# BATT_CPU.net
KiCad netlist of a schematic drawn in EAGLE
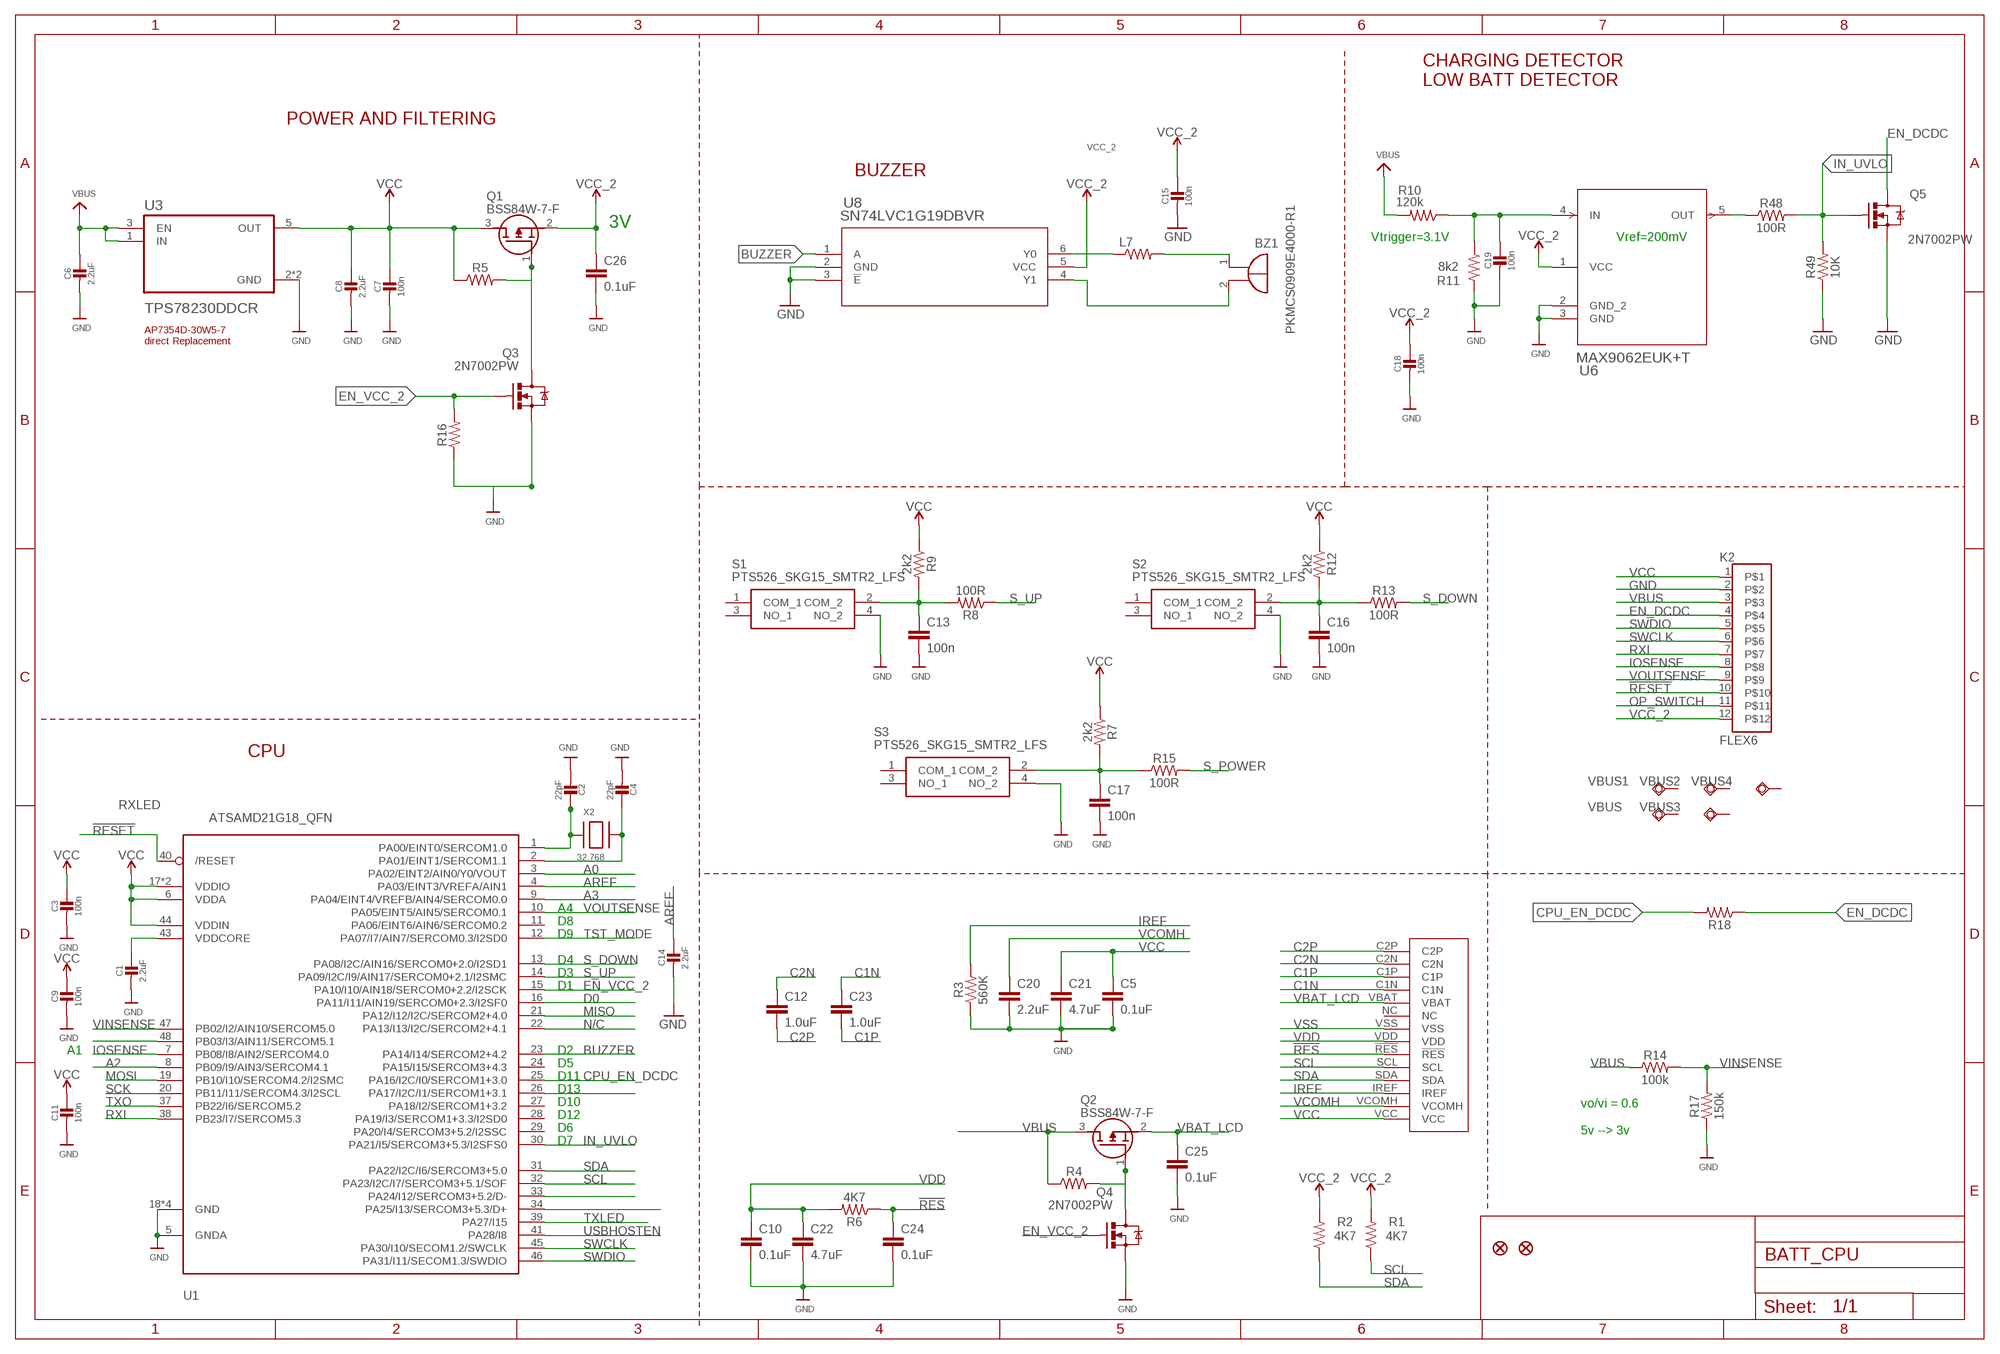
[diagram p0: schematic, sheet 1]

(export (version "E")
  (design (tool "Eeschema 10.0.6"))
  (components
    (comp (ref "BZ1")
      (value "PKMCS0909E4000-R1")
      (footprint "eagle-import:PKMCS0909")
      (libsource (lib "eagle-import") (part "PKMCS0909E4000-R1"))
    )
    (comp (ref "C1")
      (value "2.2uF")
      (footprint "eagle-import:0603-NO")
      (libsource (lib "eagle-import") (part "CAP_CERAMIC0603_NO"))
    )
    (comp (ref "C2")
      (value "22pF")
      (footprint "eagle-import:0603-NO")
      (libsource (lib "eagle-import") (part "CAP_CERAMIC0603_NO"))
    )
    (comp (ref "C3")
      (value "100n")
      (footprint "eagle-import:0603-NO")
      (libsource (lib "eagle-import") (part "CAP_CERAMIC0603_NO"))
    )
    (comp (ref "C4")
      (value "22pF")
      (footprint "eagle-import:0603-NO")
      (libsource (lib "eagle-import") (part "CAP_CERAMIC0603_NO"))
    )
    (comp (ref "C5")
      (value "0.1uF")
      (footprint "eagle-import:0402")
      (libsource (lib "eagle-import") (part "0.1UF-0402-16V-10%"))
    )
    (comp (ref "C6")
      (value "2.2uF")
      (footprint "eagle-import:0805-NO")
      (libsource (lib "eagle-import") (part "CAP_CERAMIC0805-NOOUTLINE"))
    )
    (comp (ref "C7")
      (value "100n")
      (footprint "eagle-import:0603-NO")
      (libsource (lib "eagle-import") (part "CAP_CERAMIC0603_NO"))
    )
    (comp (ref "C8")
      (value "2.2uF")
      (footprint "eagle-import:0805-NO")
      (libsource (lib "eagle-import") (part "CAP_CERAMIC0805-NOOUTLINE"))
    )
    (comp (ref "C9")
      (value "100n")
      (footprint "eagle-import:0603-NO")
      (libsource (lib "eagle-import") (part "CAP_CERAMIC0603_NO"))
    )
    (comp (ref "C10")
      (value "0.1uF")
      (footprint "eagle-import:0402")
      (libsource (lib "eagle-import") (part "0.1UF-0402-16V-10%"))
    )
    (comp (ref "C11")
      (value "100n")
      (footprint "eagle-import:0603-NO")
      (libsource (lib "eagle-import") (part "CAP_CERAMIC0603_NO"))
    )
    (comp (ref "C12")
      (value "1.0uF")
      (footprint "eagle-import:0402")
      (libsource (lib "eagle-import") (part "1.0UF-0402-16V-10%"))
    )
    (comp (ref "C13")
      (value "100n")
      (footprint "eagle-import:C0805")
      (libsource (lib "eagle-import") (part "C-EUC0805"))
    )
    (comp (ref "C14")
      (value "2.2uF")
      (footprint "eagle-import:0603-NO")
      (libsource (lib "eagle-import") (part "CAP_CERAMIC0603_NO"))
    )
    (comp (ref "C15")
      (value "100n")
      (footprint "eagle-import:0603-NO")
      (libsource (lib "eagle-import") (part "CAP_CERAMIC0603_NO"))
    )
    (comp (ref "C16")
      (value "100n")
      (footprint "eagle-import:C0805")
      (libsource (lib "eagle-import") (part "C-EUC0805"))
    )
    (comp (ref "C17")
      (value "100n")
      (footprint "eagle-import:C0805")
      (libsource (lib "eagle-import") (part "C-EUC0805"))
    )
    (comp (ref "C18")
      (value "100n")
      (footprint "eagle-import:0603-NO")
      (libsource (lib "eagle-import") (part "CAP_CERAMIC0603_NO"))
    )
    (comp (ref "C19")
      (value "100n")
      (footprint "eagle-import:0603-NO")
      (libsource (lib "eagle-import") (part "CAP_CERAMIC0603_NO"))
    )
    (comp (ref "C20")
      (value "2.2uF")
      (footprint "eagle-import:0603")
      (libsource (lib "eagle-import") (part "2.2UF-0603-10V-20%"))
    )
    (comp (ref "C21")
      (value "4.7uF")
      (footprint "eagle-import:0603")
      (libsource (lib "eagle-import") (part "4.7UF0603"))
    )
    (comp (ref "C22")
      (value "4.7uF")
      (footprint "eagle-import:0603")
      (libsource (lib "eagle-import") (part "4.7UF0603"))
    )
    (comp (ref "C23")
      (value "1.0uF")
      (footprint "eagle-import:0402")
      (libsource (lib "eagle-import") (part "1.0UF-0402-16V-10%"))
    )
    (comp (ref "C24")
      (value "0.1uF")
      (footprint "eagle-import:0402")
      (libsource (lib "eagle-import") (part "0.1UF-0402-16V-10%"))
    )
    (comp (ref "C25")
      (value "0.1uF")
      (footprint "eagle-import:0402")
      (libsource (lib "eagle-import") (part "0.1UF-0402-16V-10%"))
    )
    (comp (ref "C26")
      (value "0.1uF")
      (footprint "eagle-import:0402")
      (libsource (lib "eagle-import") (part "0.1UF-0402-16V-10%"))
    )
    (comp (ref "K2")
      (value "FLEX6")
      (footprint "eagle-import:FLEX6")
      (libsource (lib "eagle-import") (part "FLEX6"))
    )
    (comp (ref "L7")
      (value "MMZ2012Y202BT000")
      (footprint "eagle-import:0805")
      (libsource (lib "eagle-import") (part "RESISTOR0805-RES"))
    )
    (comp (ref "Q1")
      (value "BSS84W-7-F")
      (footprint "eagle-import:SOT65P222X110-3N")
      (libsource (lib "eagle-import") (part "BSS84W-7-F"))
    )
    (comp (ref "Q2")
      (value "BSS84W-7-F")
      (footprint "eagle-import:SOT65P222X110-3N")
      (libsource (lib "eagle-import") (part "BSS84W-7-F"))
    )
    (comp (ref "Q3")
      (value "2N7002PW")
      (footprint "eagle-import:SOT323")
      (libsource (lib "eagle-import") (part "MOSFET-NCHANNEL2N7002PW"))
    )
    (comp (ref "Q4")
      (value "2N7002PW")
      (footprint "eagle-import:SOT323")
      (libsource (lib "eagle-import") (part "MOSFET-NCHANNEL2N7002PW"))
    )
    (comp (ref "Q5")
      (value "2N7002PW")
      (footprint "eagle-import:SOT323")
      (libsource (lib "eagle-import") (part "MOSFET-NCHANNEL2N7002PW"))
    )
    (comp (ref "R1")
      (value "4K7")
      (footprint "eagle-import:0402")
      (libsource (lib "eagle-import") (part "RESISTOR0402"))
    )
    (comp (ref "R2")
      (value "4K7")
      (footprint "eagle-import:0402")
      (libsource (lib "eagle-import") (part "RESISTOR0402"))
    )
    (comp (ref "R3")
      (value "560K")
      (footprint "eagle-import:0402")
      (libsource (lib "eagle-import") (part "RESISTOR0402"))
    )
    (comp (ref "R4")
      (value "RESISTOR0402")
      (footprint "eagle-import:0402")
      (libsource (lib "eagle-import") (part "RESISTOR0402"))
    )
    (comp (ref "R5")
      (value "RESISTOR0402")
      (footprint "eagle-import:0402")
      (libsource (lib "eagle-import") (part "RESISTOR0402"))
    )
    (comp (ref "R6")
      (value "4K7")
      (footprint "eagle-import:0402")
      (libsource (lib "eagle-import") (part "RESISTOR0402"))
    )
    (comp (ref "R7")
      (value "2k2")
      (footprint "eagle-import:0402")
      (libsource (lib "eagle-import") (part "RESISTOR0402"))
    )
    (comp (ref "R8")
      (value "100R")
      (footprint "eagle-import:0402")
      (libsource (lib "eagle-import") (part "RESISTOR0402"))
    )
    (comp (ref "R9")
      (value "2k2")
      (footprint "eagle-import:0402")
      (libsource (lib "eagle-import") (part "RESISTOR0402"))
    )
    (comp (ref "R10")
      (value "120k")
      (footprint "eagle-import:0402")
      (libsource (lib "eagle-import") (part "RESISTOR0402"))
    )
    (comp (ref "R11")
      (value "8k2")
      (footprint "eagle-import:0402")
      (libsource (lib "eagle-import") (part "RESISTOR0402"))
    )
    (comp (ref "R12")
      (value "2k2")
      (footprint "eagle-import:0402")
      (libsource (lib "eagle-import") (part "RESISTOR0402"))
    )
    (comp (ref "R13")
      (value "100R")
      (footprint "eagle-import:0402")
      (libsource (lib "eagle-import") (part "RESISTOR0402"))
    )
    (comp (ref "R14")
      (value "100k")
      (footprint "eagle-import:0402")
      (libsource (lib "eagle-import") (part "RESISTOR0402"))
    )
    (comp (ref "R15")
      (value "100R")
      (footprint "eagle-import:0402")
      (libsource (lib "eagle-import") (part "RESISTOR0402"))
    )
    (comp (ref "R16")
      (value "RESISTOR0402")
      (footprint "eagle-import:0402")
      (libsource (lib "eagle-import") (part "RESISTOR0402"))
    )
    (comp (ref "R17")
      (value "150k")
      (footprint "eagle-import:0402")
      (libsource (lib "eagle-import") (part "RESISTOR0402"))
    )
    (comp (ref "R18")
      (value "RESISTOR0402")
      (footprint "eagle-import:0402")
      (libsource (lib "eagle-import") (part "RESISTOR0402"))
    )
    (comp (ref "R48")
      (value "100R")
      (footprint "eagle-import:0402")
      (libsource (lib "eagle-import") (part "RESISTOR0402"))
    )
    (comp (ref "R49")
      (value "10K")
      (footprint "eagle-import:0402")
      (libsource (lib "eagle-import") (part "RESISTOR0402"))
    )
    (comp (ref "S1")
      (value "PTS526_SKG15_SMTR2_LFS")
      (footprint "eagle-import:PTS526SKG15SMTR2LFS")
      (fields
        (field (name "ARROW_PART_NUMBER") "PTS526 SKG15 SMTR2 LFS")
        (field (name "MOUSER_PART_NUMBER") "611-PTS526SKG15SMR2L")
      )
      (libsource (lib "eagle-import") (part "PTS526_SKG15_SMTR2_LFS"))
    )
    (comp (ref "S2")
      (value "PTS526_SKG15_SMTR2_LFS")
      (footprint "eagle-import:PTS526SKG15SMTR2LFS")
      (fields
        (field (name "ARROW_PART_NUMBER") "PTS526 SKG15 SMTR2 LFS")
        (field (name "MOUSER_PART_NUMBER") "611-PTS526SKG15SMR2L")
      )
      (libsource (lib "eagle-import") (part "PTS526_SKG15_SMTR2_LFS"))
    )
    (comp (ref "S3")
      (value "PTS526_SKG15_SMTR2_LFS")
      (footprint "eagle-import:PTS526SKG15SMTR2LFS")
      (fields
        (field (name "ARROW_PART_NUMBER") "PTS526 SKG15 SMTR2 LFS")
        (field (name "MOUSER_PART_NUMBER") "611-PTS526SKG15SMR2L")
      )
      (libsource (lib "eagle-import") (part "PTS526_SKG15_SMTR2_LFS"))
    )
    (comp (ref "U$30")
      (value "64X32_OLED_049")
      (footprint "eagle-import:LCD_14_PINS")
      (libsource (lib "eagle-import") (part "64X32_OLED_049"))
    )
    (comp (ref "U$34")
      (value "FIDUCIAL\"\"")
      (footprint "eagle-import:FIDUCIAL_1MM")
      (libsource (lib "eagle-import") (part "FIDUCIAL{dblquote}{dblquote}"))
    )
    (comp (ref "U$35")
      (value "FIDUCIAL\"\"")
      (footprint "eagle-import:FIDUCIAL_1MM")
      (libsource (lib "eagle-import") (part "FIDUCIAL{dblquote}{dblquote}"))
    )
    (comp (ref "U1")
      (value "ATSAMD21G18_QFN")
      (footprint "eagle-import:TQFN48_7MM")
      (libsource (lib "eagle-import") (part "ATSAMD21J_QFN"))
    )
    (comp (ref "U3")
      (value "TPS78230DDCR")
      (footprint "eagle-import:SOT95P280X110-5N")
      (fields (field (name "MF") "Texas Instruments"))
      (libsource (lib "eagle-import") (part "TPS78230DDCR"))
    )
    (comp (ref "U6")
      (value "MAX9062EUK+T")
      (footprint "eagle-import:21-0057F_MXM")
      (libsource (lib "eagle-import") (part "MAX9062EUK+T"))
    )
    (comp (ref "U8")
      (value "SN74LVC1G19DBVR")
      (footprint "eagle-import:DBV6")
      (fields
        (field (name "GENERIC_PART_NUMBER") "SN74LVC1G19")
        (field (name "MANUFACTURER") "Texas Instruments")
      )
      (libsource (lib "eagle-import") (part "SN74LVC1G19DBVR"))
    )
    (comp (ref "VBUS")
      (value "TESTPAD_TPSQB1,27")
      (footprint "eagle-import:TESTPAD_B1,27")
      (libsource (lib "eagle-import") (part "TESTPAD_TPSQB1,27"))
    )
    (comp (ref "VBUS1")
      (value "TESTPAD_TPSQB1,27")
      (footprint "eagle-import:TESTPAD_B1,27")
      (libsource (lib "eagle-import") (part "TESTPAD_TPSQB1,27"))
    )
    (comp (ref "VBUS2")
      (value "TESTPAD_TPSQB1,27")
      (footprint "eagle-import:TESTPAD_B1,27")
      (libsource (lib "eagle-import") (part "TESTPAD_TPSQB1,27"))
    )
    (comp (ref "VBUS3")
      (value "TESTPAD_TPSQB1,27")
      (footprint "eagle-import:TESTPAD_B1,27")
      (libsource (lib "eagle-import") (part "TESTPAD_TPSQB1,27"))
    )
    (comp (ref "VBUS4")
      (value "TESTPAD_TPSQB1,27")
      (footprint "eagle-import:TESTPAD_B1,27")
      (libsource (lib "eagle-import") (part "TESTPAD_TPSQB1,27"))
    )
    (comp (ref "X2")
      (value "32.768")
      (footprint "eagle-import:XTAL3215")
      (libsource (lib "eagle-import") (part "XTAL-3.2X1.5"))
    )
  )
  (nets
    (net (code "1") (name "/A0") (class "Default")
      (node (ref "U1") (pin "3") (pinfunction "PA02/EINT2/AIN0/Y0/VOUT_3") (pintype "bidirectional"))
    )
    (net (code "2") (name "/A2") (class "Default")
      (node (ref "U1") (pin "8") (pinfunction "PB09/I9/AIN3/SERCOM4.1_8") (pintype "bidirectional"))
    )
    (net (code "3") (name "/A3") (class "Default")
      (node (ref "U1") (pin "9") (pinfunction "PA04/EINT4/VREFB/AIN4/SERCOM0.0_9") (pintype "bidirectional"))
    )
    (net (code "4") (name "/AREF") (class "Default")
      (node (ref "C14") (pin "1") (pinfunction "1_1") (pintype "passive"))
      (node (ref "U1") (pin "4") (pinfunction "PA03/EINT3/VREFA/AIN1_4") (pintype "bidirectional"))
    )
    (net (code "5") (name "/C1N") (class "Default")
      (node (ref "C23") (pin "1") (pinfunction "1_1") (pintype "passive"))
      (node (ref "U$30") (pin "C1N") (pinfunction "C1N_C1N") (pintype "bidirectional"))
    )
    (net (code "6") (name "/C1P") (class "Default")
      (node (ref "C23") (pin "2") (pinfunction "2_2") (pintype "passive"))
      (node (ref "U$30") (pin "C1P") (pinfunction "C1P_C1P") (pintype "bidirectional"))
    )
    (net (code "7") (name "/C2N") (class "Default")
      (node (ref "C12") (pin "1") (pinfunction "1_1") (pintype "passive"))
      (node (ref "U$30") (pin "C2N") (pinfunction "C2N_C2N") (pintype "bidirectional"))
    )
    (net (code "8") (name "/C2P") (class "Default")
      (node (ref "C12") (pin "2") (pinfunction "2_2") (pintype "passive"))
      (node (ref "U$30") (pin "C2P") (pinfunction "C2P_C2P") (pintype "bidirectional"))
    )
    (net (code "9") (name "/D0") (class "Default")
      (node (ref "U1") (pin "16") (pinfunction "PA11/I11/AIN19/SERCOM0+2.3/I2SF0_16") (pintype "bidirectional"))
    )
    (net (code "10") (name "/IOSENSE") (class "Default")
      (node (ref "K2") (pin "8") (pinfunction "P$8_8") (pintype "bidirectional"))
      (node (ref "U1") (pin "7") (pinfunction "PB08/I8/AIN2/SERCOM4.0_7") (pintype "bidirectional"))
    )
    (net (code "11") (name "/IREF") (class "Default")
      (node (ref "R3") (pin "2") (pinfunction "2_2") (pintype "passive"))
      (node (ref "U$30") (pin "IREF") (pinfunction "IREF_IREF") (pintype "bidirectional"))
    )
    (net (code "12") (name "/MISO") (class "Default")
      (node (ref "U1") (pin "21") (pinfunction "PA12/I12/I2C/SERCOM2+4.0_21") (pintype "bidirectional"))
    )
    (net (code "13") (name "/MOSI") (class "Default")
      (node (ref "U1") (pin "19") (pinfunction "PB10/I10/SERCOM4.2/I2SMC_19") (pintype "bidirectional"))
    )
    (net (code "14") (name "/OP_SWITCH") (class "Default")
      (node (ref "K2") (pin "11") (pinfunction "P$11_11") (pintype "bidirectional"))
      (node (ref "U1") (pin "26") (pinfunction "PA17/I2C/I1/SERCOM1+3.1_26") (pintype "bidirectional"))
    )
    (net (code "15") (name "/RXI") (class "Default")
      (node (ref "K2") (pin "7") (pinfunction "P$7_7") (pintype "bidirectional"))
      (node (ref "U1") (pin "38") (pinfunction "PB23/I7/SERCOM5.3_38") (pintype "bidirectional"))
    )
    (net (code "16") (name "/SCK") (class "Default")
      (node (ref "U1") (pin "20") (pinfunction "PB11/I11/SERCOM4.3/I2SCL_20") (pintype "bidirectional"))
    )
    (net (code "17") (name "/SCL") (class "Default")
      (node (ref "R1") (pin "1") (pinfunction "1_1") (pintype "passive"))
      (node (ref "U$30") (pin "SCL") (pinfunction "SCL_SCL") (pintype "bidirectional"))
      (node (ref "U1") (pin "32") (pinfunction "PA23/I2C/I7/SERCOM3+5.1/SOF_32") (pintype "bidirectional"))
    )
    (net (code "18") (name "/SDA") (class "Default")
      (node (ref "R2") (pin "1") (pinfunction "1_1") (pintype "passive"))
      (node (ref "U$30") (pin "SDA") (pinfunction "SDA_SDA") (pintype "bidirectional"))
      (node (ref "U1") (pin "31") (pinfunction "PA22/I2C/I6/SERCOM3+5.0_31") (pintype "bidirectional"))
    )
    (net (code "19") (name "/SWCLK") (class "Default")
      (node (ref "K2") (pin "6") (pinfunction "P$6_6") (pintype "bidirectional"))
      (node (ref "U1") (pin "45") (pinfunction "PA30/I10/SECOM1.2/SWCLK_45") (pintype "bidirectional"))
    )
    (net (code "20") (name "/SWDIO") (class "Default")
      (node (ref "K2") (pin "5") (pinfunction "P$5_5") (pintype "bidirectional"))
      (node (ref "U1") (pin "46") (pinfunction "PA31/I11/SECOM1.3/SWDIO_46") (pintype "bidirectional"))
    )
    (net (code "21") (name "/S_DOWN") (class "Default")
      (node (ref "R13") (pin "2") (pinfunction "2_2") (pintype "passive"))
      (node (ref "U1") (pin "13") (pinfunction "PA08/I2C/AIN16/SERCOM0+2.0/I2SD1_13") (pintype "bidirectional"))
    )
    (net (code "22") (name "/S_POWER") (class "Default")
      (node (ref "R15") (pin "2") (pinfunction "2_2") (pintype "passive"))
    )
    (net (code "23") (name "/S_UP") (class "Default")
      (node (ref "R8") (pin "1") (pinfunction "1_1") (pintype "passive"))
      (node (ref "U1") (pin "14") (pinfunction "PA09/I2C/I9/AIN17/SERCOM0+2.1/I2SMC_14") (pintype "bidirectional"))
    )
    (net (code "24") (name "/TST_MODE") (class "Default")
      (node (ref "U1") (pin "12") (pinfunction "PA07/I7/AIN7/SERCOM0.3/I2SD0_12") (pintype "bidirectional"))
    )
    (net (code "25") (name "/TXO") (class "Default")
      (node (ref "U1") (pin "37") (pinfunction "PB22/I6/SERCOM5.2_37") (pintype "bidirectional"))
    )
    (net (code "26") (name "/VBAT_LCD") (class "Default")
      (node (ref "C25") (pin "1") (pinfunction "1_1") (pintype "passive"))
      (node (ref "Q2") (pin "2") (pinfunction "S_2") (pintype "bidirectional"))
      (node (ref "U$30") (pin "VBAT") (pinfunction "VBAT_VBAT") (pintype "bidirectional"))
    )
    (net (code "27") (name "/VCOMH") (class "Default")
      (node (ref "C20") (pin "1") (pinfunction "1_1") (pintype "passive"))
      (node (ref "U$30") (pin "VCOMH") (pinfunction "VCOMH_VCOMH") (pintype "bidirectional"))
    )
    (net (code "28") (name "/VDD") (class "Default")
      (node (ref "C10") (pin "1") (pinfunction "1_1") (pintype "passive"))
      (node (ref "C22") (pin "1") (pinfunction "1_1") (pintype "passive"))
      (node (ref "R6") (pin "2") (pinfunction "2_2") (pintype "passive"))
      (node (ref "U$30") (pin "VDD") (pinfunction "VDD_VDD") (pintype "bidirectional"))
    )
    (net (code "29") (name "/VINSENSE") (class "Default")
      (node (ref "R14") (pin "2") (pinfunction "2_2") (pintype "passive"))
      (node (ref "R17") (pin "2") (pinfunction "2_2") (pintype "passive"))
      (node (ref "U1") (pin "47") (pinfunction "PB02/I2/AIN10/SERCOM5.0_47") (pintype "bidirectional"))
    )
    (net (code "30") (name "/VOUTSENSE") (class "Default")
      (node (ref "K2") (pin "9") (pinfunction "P$9_9") (pintype "bidirectional"))
      (node (ref "U1") (pin "10") (pinfunction "PA05/EINT5/AIN5/SERCOM0.1_10") (pintype "bidirectional"))
    )
    (net (code "31") (name "/VSS") (class "Default")
      (node (ref "U$30") (pin "VSS") (pinfunction "VSS_VSS") (pintype "bidirectional"))
    )
    (net (code "32") (name "/~{RESET}") (class "Default")
      (node (ref "K2") (pin "10") (pinfunction "P$10_10") (pintype "bidirectional"))
      (node (ref "U1") (pin "40") (pinfunction "/RESET_40") (pintype "bidirectional"))
    )
    (net (code "33") (name "/~{RES}") (class "Default")
      (node (ref "C24") (pin "1") (pinfunction "1_1") (pintype "passive"))
      (node (ref "R6") (pin "1") (pinfunction "1_1") (pintype "passive"))
      (node (ref "U$30") (pin "!RES") (pinfunction "~{RES}_!RES") (pintype "bidirectional"))
    )
    (net (code "34") (name "BUZZER") (class "Default")
      (node (ref "U1") (pin "23") (pinfunction "PA14/I14/SERCOM2+4.2_23") (pintype "bidirectional"))
      (node (ref "U8") (pin "1") (pinfunction "A_1") (pintype "input"))
    )
    (net (code "35") (name "CPU_EN_DCDC") (class "Default")
      (node (ref "R18") (pin "2") (pinfunction "2_2") (pintype "passive"))
      (node (ref "U1") (pin "25") (pinfunction "PA16/I2C/I0/SERCOM1+3.0_25") (pintype "bidirectional"))
    )
    (net (code "36") (name "EN_DCDC") (class "Default")
      (node (ref "K2") (pin "4") (pinfunction "P$4_4") (pintype "bidirectional"))
      (node (ref "Q5") (pin "3") (pinfunction "D_3") (pintype "passive"))
      (node (ref "R18") (pin "1") (pinfunction "1_1") (pintype "passive"))
    )
    (net (code "37") (name "EN_VCC_2") (class "Default")
      (node (ref "Q3") (pin "1") (pinfunction "G_1") (pintype "passive"))
      (node (ref "Q4") (pin "1") (pinfunction "G_1") (pintype "passive"))
      (node (ref "R16") (pin "2") (pinfunction "2_2") (pintype "passive"))
      (node (ref "U1") (pin "15") (pinfunction "PA10/I10/AIN18/SERCOM0+2.2/I2SCK_15") (pintype "bidirectional"))
    )
    (net (code "38") (name "GND") (class "Default")
      (node (ref "C1") (pin "2") (pinfunction "2_2") (pintype "passive"))
      (node (ref "C10") (pin "2") (pinfunction "2_2") (pintype "passive"))
      (node (ref "C11") (pin "2") (pinfunction "2_2") (pintype "passive"))
      (node (ref "C13") (pin "2") (pinfunction "2_2") (pintype "passive"))
      (node (ref "C14") (pin "2") (pinfunction "2_2") (pintype "passive"))
      (node (ref "C15") (pin "2") (pinfunction "2_2") (pintype "passive"))
      (node (ref "C16") (pin "2") (pinfunction "2_2") (pintype "passive"))
      (node (ref "C17") (pin "2") (pinfunction "2_2") (pintype "passive"))
      (node (ref "C18") (pin "2") (pinfunction "2_2") (pintype "passive"))
      (node (ref "C19") (pin "2") (pinfunction "2_2") (pintype "passive"))
      (node (ref "C2") (pin "2") (pinfunction "2_2") (pintype "passive"))
      (node (ref "C20") (pin "2") (pinfunction "2_2") (pintype "passive"))
      (node (ref "C21") (pin "2") (pinfunction "2_2") (pintype "passive"))
      (node (ref "C22") (pin "2") (pinfunction "2_2") (pintype "passive"))
      (node (ref "C24") (pin "2") (pinfunction "2_2") (pintype "passive"))
      (node (ref "C25") (pin "2") (pinfunction "2_2") (pintype "passive"))
      (node (ref "C26") (pin "2") (pinfunction "2_2") (pintype "passive"))
      (node (ref "C3") (pin "2") (pinfunction "2_2") (pintype "passive"))
      (node (ref "C4") (pin "2") (pinfunction "2_2") (pintype "passive"))
      (node (ref "C5") (pin "2") (pinfunction "2_2") (pintype "passive"))
      (node (ref "C6") (pin "2") (pinfunction "2_2") (pintype "passive"))
      (node (ref "C7") (pin "2") (pinfunction "2_2") (pintype "passive"))
      (node (ref "C8") (pin "2") (pinfunction "2_2") (pintype "passive"))
      (node (ref "C9") (pin "2") (pinfunction "2_2") (pintype "passive"))
      (node (ref "K2") (pin "2") (pinfunction "P$2_2") (pintype "bidirectional"))
      (node (ref "Q3") (pin "2") (pinfunction "S_2") (pintype "passive"))
      (node (ref "Q4") (pin "2") (pinfunction "S_2") (pintype "passive"))
      (node (ref "Q5") (pin "2") (pinfunction "S_2") (pintype "passive"))
      (node (ref "R11") (pin "2") (pinfunction "2_2") (pintype "passive"))
      (node (ref "R16") (pin "1") (pinfunction "1_1") (pintype "passive"))
      (node (ref "R17") (pin "1") (pinfunction "1_1") (pintype "passive"))
      (node (ref "R3") (pin "1") (pinfunction "1_1") (pintype "passive"))
      (node (ref "R49") (pin "1") (pinfunction "1_1") (pintype "passive"))
      (node (ref "S1") (pin "4") (pinfunction "NO_2_4") (pintype "bidirectional"))
      (node (ref "S2") (pin "4") (pinfunction "NO_2_4") (pintype "bidirectional"))
      (node (ref "S3") (pin "4") (pinfunction "NO_2_4") (pintype "bidirectional"))
      (node (ref "U1") (pin "18") (pinfunction "GND_18") (pintype "power_in"))
      (node (ref "U1") (pin "35") (pinfunction "GND_35") (pintype "power_in"))
      (node (ref "U1") (pin "42") (pinfunction "GND_42") (pintype "power_in"))
      (node (ref "U1") (pin "5") (pinfunction "GNDA_5") (pintype "power_in"))
      (node (ref "U1") (pin "THERMAL") (pinfunction "GND_THERMAL") (pintype "power_in"))
      (node (ref "U3") (pin "2") (pinfunction "GND_2") (pintype "power_in"))
      (node (ref "U3") (pin "4") (pinfunction "GND_4") (pintype "power_in"))
      (node (ref "U6") (pin "2") (pinfunction "GND_2_2") (pintype "power_in"))
      (node (ref "U6") (pin "3") (pinfunction "GND_3") (pintype "power_in"))
      (node (ref "U8") (pin "2") (pinfunction "GND_2") (pintype "power_in"))
      (node (ref "U8") (pin "3") (pinfunction "~{E}_3") (pintype "input"))
    )
    (net (code "39") (name "IN_UVLO") (class "Default")
      (node (ref "Q5") (pin "1") (pinfunction "G_1") (pintype "passive"))
      (node (ref "R48") (pin "2") (pinfunction "2_2") (pintype "passive"))
      (node (ref "R49") (pin "2") (pinfunction "2_2") (pintype "passive"))
      (node (ref "U1") (pin "30") (pinfunction "PA21/I5/SERCOM3+5.3/I2SFS0_30") (pintype "bidirectional"))
    )
    (net (code "40") (name "Net-(BZ1-+)") (class "Default")
      (node (ref "BZ1") (pin "1") (pinfunction "+_1") (pintype "passive"))
      (node (ref "L7") (pin "2") (pinfunction "2_2") (pintype "passive"))
    )
    (net (code "41") (name "Net-(BZ1--)") (class "Default")
      (node (ref "BZ1") (pin "2") (pinfunction "-_2") (pintype "passive"))
      (node (ref "U8") (pin "4") (pinfunction "Y1_4") (pintype "output"))
    )
    (net (code "42") (name "Net-(Q1-G)") (class "Default")
      (node (ref "Q1") (pin "1") (pinfunction "G_1") (pintype "bidirectional"))
      (node (ref "Q3") (pin "3") (pinfunction "D_3") (pintype "passive"))
      (node (ref "R5") (pin "2") (pinfunction "2_2") (pintype "passive"))
    )
    (net (code "43") (name "Net-(Q2-G)") (class "Default")
      (node (ref "Q2") (pin "1") (pinfunction "G_1") (pintype "bidirectional"))
      (node (ref "Q4") (pin "3") (pinfunction "D_3") (pintype "passive"))
      (node (ref "R4") (pin "2") (pinfunction "2_2") (pintype "passive"))
    )
    (net (code "44") (name "Net-(S1-COM_2)") (class "Default")
      (node (ref "C13") (pin "1") (pinfunction "1_1") (pintype "passive"))
      (node (ref "R8") (pin "2") (pinfunction "2_2") (pintype "passive"))
      (node (ref "R9") (pin "2") (pinfunction "2_2") (pintype "passive"))
      (node (ref "S1") (pin "2") (pinfunction "COM_2_2") (pintype "bidirectional"))
    )
    (net (code "45") (name "Net-(S2-COM_2)") (class "Default")
      (node (ref "C16") (pin "1") (pinfunction "1_1") (pintype "passive"))
      (node (ref "R12") (pin "2") (pinfunction "2_2") (pintype "passive"))
      (node (ref "R13") (pin "1") (pinfunction "1_1") (pintype "passive"))
      (node (ref "S2") (pin "2") (pinfunction "COM_2_2") (pintype "bidirectional"))
    )
    (net (code "46") (name "Net-(S3-COM_2)") (class "Default")
      (node (ref "C17") (pin "1") (pinfunction "1_1") (pintype "passive"))
      (node (ref "R15") (pin "1") (pinfunction "1_1") (pintype "passive"))
      (node (ref "R7") (pin "2") (pinfunction "2_2") (pintype "passive"))
      (node (ref "S3") (pin "2") (pinfunction "COM_2_2") (pintype "bidirectional"))
    )
    (net (code "47") (name "Net-(U1-PA00{slash}EINT0{slash}SERCOM1.0)") (class "Default")
      (node (ref "C2") (pin "1") (pinfunction "1_1") (pintype "passive"))
      (node (ref "U1") (pin "1") (pinfunction "PA00/EINT0/SERCOM1.0_1") (pintype "bidirectional"))
      (node (ref "X2") (pin "P$1") (pinfunction "P$1_P$1") (pintype "bidirectional"))
    )
    (net (code "48") (name "Net-(U1-PA01{slash}EINT1{slash}SERCOM1.1)") (class "Default")
      (node (ref "C4") (pin "1") (pinfunction "1_1") (pintype "passive"))
      (node (ref "U1") (pin "2") (pinfunction "PA01/EINT1/SERCOM1.1_2") (pintype "bidirectional"))
      (node (ref "X2") (pin "P$2") (pinfunction "P$2_P$2") (pintype "bidirectional"))
    )
    (net (code "49") (name "Net-(U1-VDDCORE)") (class "Default")
      (node (ref "C1") (pin "1") (pinfunction "1_1") (pintype "passive"))
      (node (ref "U1") (pin "43") (pinfunction "VDDCORE_43") (pintype "power_in"))
    )
    (net (code "50") (name "Net-(U6-IN)") (class "Default")
      (node (ref "C19") (pin "1") (pinfunction "1_1") (pintype "passive"))
      (node (ref "R10") (pin "1") (pinfunction "1_1") (pintype "passive"))
      (node (ref "R11") (pin "1") (pinfunction "1_1") (pintype "passive"))
      (node (ref "U6") (pin "4") (pinfunction "IN_4") (pintype "input"))
    )
    (net (code "51") (name "Net-(U6-OUT)") (class "Default")
      (node (ref "R48") (pin "1") (pinfunction "1_1") (pintype "passive"))
      (node (ref "U6") (pin "5") (pinfunction "OUT_5") (pintype "output"))
    )
    (net (code "52") (name "Net-(U8-Y0)") (class "Default")
      (node (ref "L7") (pin "1") (pinfunction "1_1") (pintype "passive"))
      (node (ref "U8") (pin "6") (pinfunction "Y0_6") (pintype "output"))
    )
    (net (code "53") (name "VBUS") (class "Default")
      (node (ref "C6") (pin "1") (pinfunction "1_1") (pintype "passive"))
      (node (ref "K2") (pin "3") (pinfunction "P$3_3") (pintype "bidirectional"))
      (node (ref "Q2") (pin "3") (pinfunction "D_3") (pintype "bidirectional"))
      (node (ref "R10") (pin "2") (pinfunction "2_2") (pintype "passive"))
      (node (ref "R14") (pin "1") (pinfunction "1_1") (pintype "passive"))
      (node (ref "R4") (pin "1") (pinfunction "1_1") (pintype "passive"))
      (node (ref "U3") (pin "1") (pinfunction "IN_1") (pintype "input"))
      (node (ref "U3") (pin "3") (pinfunction "EN_3") (pintype "input"))
    )
    (net (code "54") (name "VCC") (class "Default")
      (node (ref "C11") (pin "1") (pinfunction "1_1") (pintype "passive"))
      (node (ref "C21") (pin "1") (pinfunction "1_1") (pintype "passive"))
      (node (ref "C3") (pin "1") (pinfunction "1_1") (pintype "passive"))
      (node (ref "C5") (pin "1") (pinfunction "1_1") (pintype "passive"))
      (node (ref "C7") (pin "1") (pinfunction "1_1") (pintype "passive"))
      (node (ref "C8") (pin "1") (pinfunction "1_1") (pintype "passive"))
      (node (ref "C9") (pin "1") (pinfunction "1_1") (pintype "passive"))
      (node (ref "K2") (pin "1") (pinfunction "P$1_1") (pintype "bidirectional"))
      (node (ref "Q1") (pin "3") (pinfunction "D_3") (pintype "bidirectional"))
      (node (ref "R12") (pin "1") (pinfunction "1_1") (pintype "passive"))
      (node (ref "R5") (pin "1") (pinfunction "1_1") (pintype "passive"))
      (node (ref "R7") (pin "1") (pinfunction "1_1") (pintype "passive"))
      (node (ref "R9") (pin "1") (pinfunction "1_1") (pintype "passive"))
      (node (ref "U$30") (pin "VCC") (pinfunction "VCC_VCC") (pintype "bidirectional"))
      (node (ref "U1") (pin "17") (pinfunction "VDDIO_17") (pintype "power_in"))
      (node (ref "U1") (pin "36") (pinfunction "VDDIO_36") (pintype "power_in"))
      (node (ref "U1") (pin "44") (pinfunction "VDDIN_44") (pintype "power_in"))
      (node (ref "U1") (pin "6") (pinfunction "VDDA_6") (pintype "power_in"))
      (node (ref "U3") (pin "5") (pinfunction "OUT_5") (pintype "output"))
    )
    (net (code "55") (name "VCC_2") (class "Default")
      (node (ref "C15") (pin "1") (pinfunction "1_1") (pintype "passive"))
      (node (ref "C18") (pin "1") (pinfunction "1_1") (pintype "passive"))
      (node (ref "C26") (pin "1") (pinfunction "1_1") (pintype "passive"))
      (node (ref "K2") (pin "12") (pinfunction "P$12_12") (pintype "bidirectional"))
      (node (ref "Q1") (pin "2") (pinfunction "S_2") (pintype "bidirectional"))
      (node (ref "R1") (pin "2") (pinfunction "2_2") (pintype "passive"))
      (node (ref "R2") (pin "2") (pinfunction "2_2") (pintype "passive"))
      (node (ref "U6") (pin "1") (pinfunction "VCC_1") (pintype "power_in"))
      (node (ref "U8") (pin "5") (pinfunction "VCC_5") (pintype "power_in"))
    )
    (net (code "56") (name "unconnected-(S1-COM_1-Pad1)") (class "Default")
      (node (ref "S1") (pin "1") (pinfunction "COM_1_1") (pintype "bidirectional"))
    )
    (net (code "57") (name "unconnected-(S1-NO_1-Pad3)") (class "Default")
      (node (ref "S1") (pin "3") (pinfunction "NO_1_3") (pintype "bidirectional"))
    )
    (net (code "58") (name "unconnected-(S2-COM_1-Pad1)") (class "Default")
      (node (ref "S2") (pin "1") (pinfunction "COM_1_1") (pintype "bidirectional"))
    )
    (net (code "59") (name "unconnected-(S2-NO_1-Pad3)") (class "Default")
      (node (ref "S2") (pin "3") (pinfunction "NO_1_3") (pintype "bidirectional"))
    )
    (net (code "60") (name "unconnected-(S3-COM_1-Pad1)") (class "Default")
      (node (ref "S3") (pin "1") (pinfunction "COM_1_1") (pintype "bidirectional"))
    )
    (net (code "61") (name "unconnected-(S3-NO_1-Pad3)") (class "Default")
      (node (ref "S3") (pin "3") (pinfunction "NO_1_3") (pintype "bidirectional"))
    )
    (net (code "62") (name "unconnected-(U$30-PadNC)") (class "Default")
      (node (ref "U$30") (pin "NC") (pinfunction "NC_NC") (pintype "bidirectional"))
    )
    (net (code "63") (name "unconnected-(U1-PA06{slash}EINT6{slash}AIN6{slash}SERCOM0.2-Pad11)") (class "Default")
      (node (ref "U1") (pin "11") (pinfunction "PA06/EINT6/AIN6/SERCOM0.2_11") (pintype "bidirectional"))
    )
    (net (code "64") (name "unconnected-(U1-PA13{slash}I13{slash}I2C{slash}SERCOM2+4.1-Pad22)") (class "Default")
      (node (ref "U1") (pin "22") (pinfunction "PA13/I13/I2C/SERCOM2+4.1_22") (pintype "bidirectional"))
    )
    (net (code "65") (name "unconnected-(U1-PA15{slash}I15{slash}SERCOM3+4.3-Pad24)") (class "Default")
      (node (ref "U1") (pin "24") (pinfunction "PA15/I15/SERCOM3+4.3_24") (pintype "bidirectional"))
    )
    (net (code "66") (name "unconnected-(U1-PA18{slash}I2{slash}SERCOM1+3.2-Pad27)") (class "Default")
      (node (ref "U1") (pin "27") (pinfunction "PA18/I2/SERCOM1+3.2_27") (pintype "bidirectional"))
    )
    (net (code "67") (name "unconnected-(U1-PA19{slash}I3{slash}SERCOM1+3.3{slash}I2SD0-Pad28)") (class "Default")
      (node (ref "U1") (pin "28") (pinfunction "PA19/I3/SERCOM1+3.3/I2SD0_28") (pintype "bidirectional"))
    )
    (net (code "68") (name "unconnected-(U1-PA20{slash}I4{slash}SERCOM3+5.2{slash}I2SSC-Pad29)") (class "Default")
      (node (ref "U1") (pin "29") (pinfunction "PA20/I4/SERCOM3+5.2/I2SSC_29") (pintype "bidirectional"))
    )
    (net (code "69") (name "unconnected-(U1-PA24{slash}I12{slash}SERCOM3+5.2{slash}D--Pad33)") (class "Default")
      (node (ref "U1") (pin "33") (pinfunction "PA24/I12/SERCOM3+5.2/D-_33") (pintype "bidirectional"))
    )
    (net (code "70") (name "unconnected-(U1-PA25{slash}I13{slash}SERCOM3+5.3{slash}D+-Pad34)") (class "Default")
      (node (ref "U1") (pin "34") (pinfunction "PA25/I13/SERCOM3+5.3/D+_34") (pintype "bidirectional"))
    )
    (net (code "71") (name "unconnected-(U1-PA27{slash}I15-Pad39)") (class "Default")
      (node (ref "U1") (pin "39") (pinfunction "PA27/I15_39") (pintype "bidirectional"))
    )
    (net (code "72") (name "unconnected-(U1-PA28{slash}I8-Pad41)") (class "Default")
      (node (ref "U1") (pin "41") (pinfunction "PA28/I8_41") (pintype "bidirectional"))
    )
    (net (code "73") (name "unconnected-(U1-PB03{slash}I3{slash}AIN11{slash}SERCOM5.1-Pad48)") (class "Default")
      (node (ref "U1") (pin "48") (pinfunction "PB03/I3/AIN11/SERCOM5.1_48") (pintype "bidirectional"))
    )
    (net (code "74") (name "unconnected-(VBUS-PadTP)") (class "Default")
      (node (ref "VBUS") (pin "TP") (pinfunction "TP_TP") (pintype "input"))
    )
    (net (code "75") (name "unconnected-(VBUS1-PadTP)") (class "Default")
      (node (ref "VBUS1") (pin "TP") (pinfunction "TP_TP") (pintype "input"))
    )
    (net (code "76") (name "unconnected-(VBUS2-PadTP)") (class "Default")
      (node (ref "VBUS2") (pin "TP") (pinfunction "TP_TP") (pintype "input"))
    )
    (net (code "77") (name "unconnected-(VBUS3-PadTP)") (class "Default")
      (node (ref "VBUS3") (pin "TP") (pinfunction "TP_TP") (pintype "input"))
    )
    (net (code "78") (name "unconnected-(VBUS4-PadTP)") (class "Default")
      (node (ref "VBUS4") (pin "TP") (pinfunction "TP_TP") (pintype "input"))
    )
  )
)
